# 1_3_prelab.net
KiCad netlist of a schematic drawn in Altium Designer
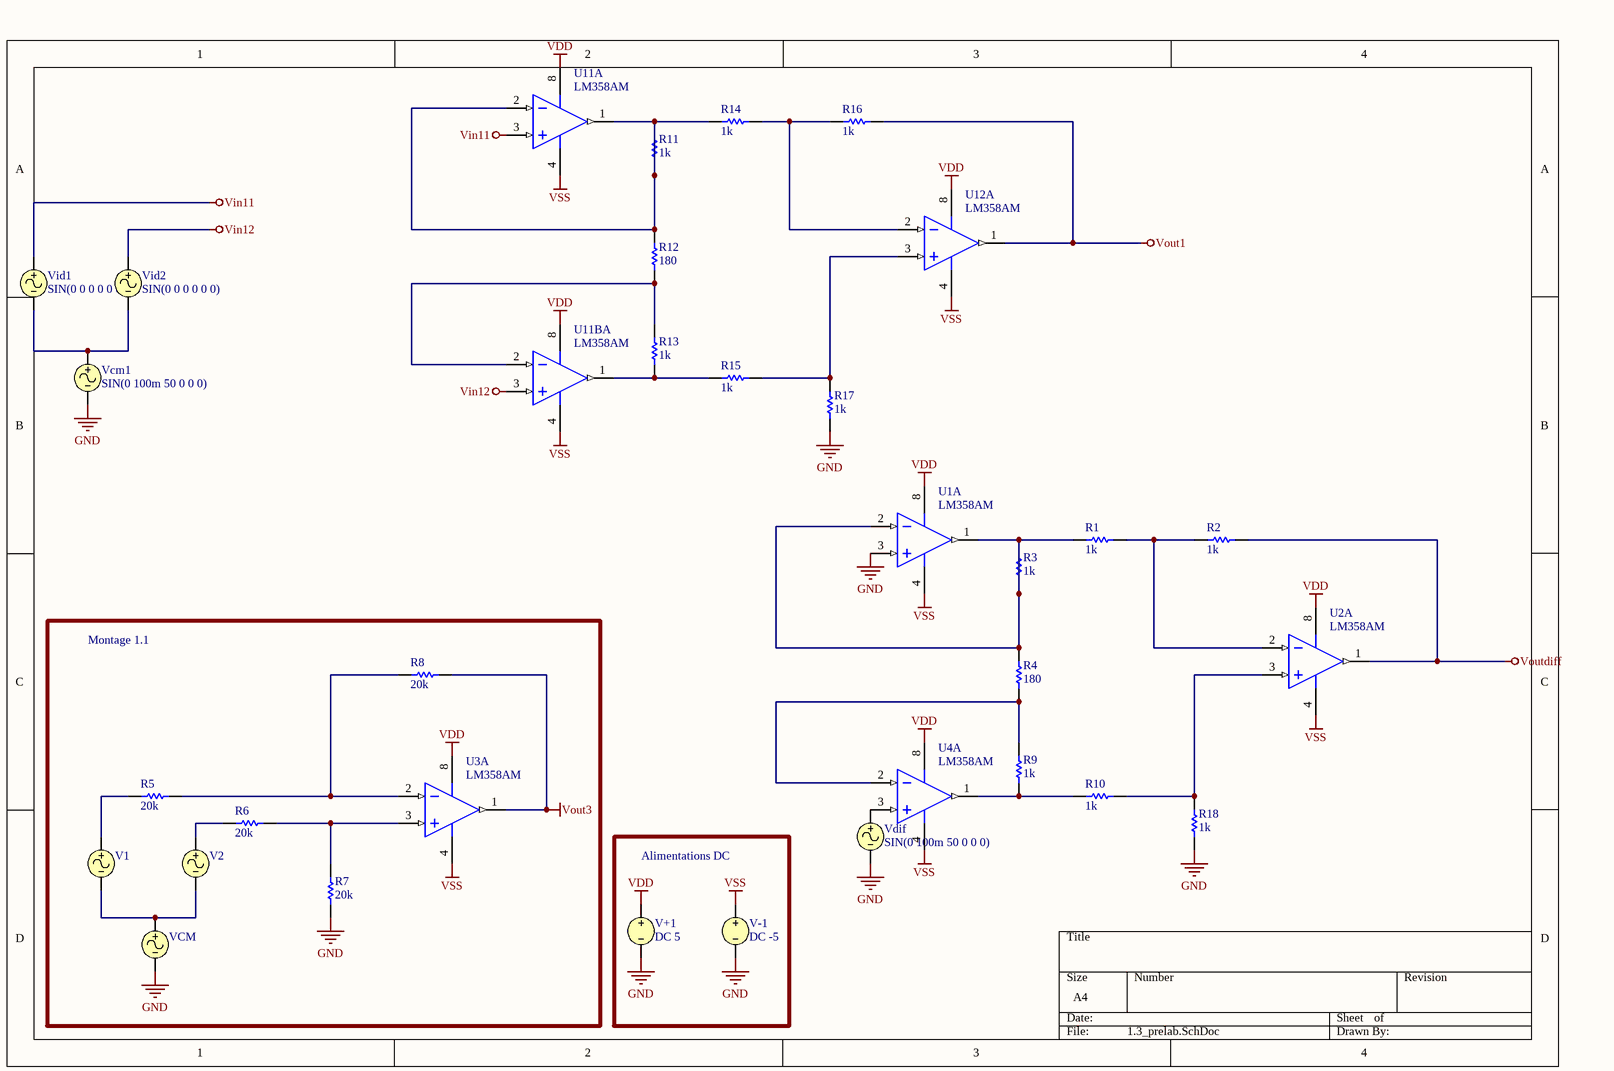
[diagram p0: 1.3_prelab.SchDoc]

(export (version "E")
  (design (tool "Eeschema 10.0.6"))
  (components
    (comp (ref "R1")
      (value "1k")
      (description "Resistor")
      (libsource (lib "Simulation Generic Components") (part "Resistor"))
    )
    (comp (ref "R2")
      (value "1k")
      (description "Resistor")
      (libsource (lib "Simulation Generic Components") (part "Resistor"))
    )
    (comp (ref "R3")
      (value "1k")
      (description "Resistor")
      (libsource (lib "Simulation Generic Components") (part "Resistor"))
    )
    (comp (ref "R4")
      (value "180")
      (description "Resistor")
      (libsource (lib "Simulation Generic Components") (part "Resistor"))
    )
    (comp (ref "R5")
      (value "20k")
      (description "Resistor")
      (libsource (lib "Simulation Generic Components") (part "Resistor"))
    )
    (comp (ref "R6")
      (value "20k")
      (description "Resistor")
      (libsource (lib "Simulation Generic Components") (part "Resistor"))
    )
    (comp (ref "R7")
      (value "20k")
      (description "Resistor")
      (libsource (lib "Simulation Generic Components") (part "Resistor"))
    )
    (comp (ref "R8")
      (value "20k")
      (description "Resistor")
      (libsource (lib "Simulation Generic Components") (part "Resistor"))
    )
    (comp (ref "R9")
      (value "1k")
      (description "Resistor")
      (libsource (lib "Simulation Generic Components") (part "Resistor"))
    )
    (comp (ref "R10")
      (value "1k")
      (description "Resistor")
      (libsource (lib "Simulation Generic Components") (part "Resistor"))
    )
    (comp (ref "R11")
      (value "1k")
      (description "Resistor")
      (libsource (lib "Simulation Generic Components") (part "Resistor"))
    )
    (comp (ref "R12")
      (value "180")
      (description "Resistor")
      (libsource (lib "Simulation Generic Components") (part "Resistor"))
    )
    (comp (ref "R13")
      (value "1k")
      (description "Resistor")
      (libsource (lib "Simulation Generic Components") (part "Resistor"))
    )
    (comp (ref "R14")
      (value "1k")
      (description "Resistor")
      (libsource (lib "Simulation Generic Components") (part "Resistor"))
    )
    (comp (ref "R15")
      (value "1k")
      (description "Resistor")
      (libsource (lib "Simulation Generic Components") (part "Resistor"))
    )
    (comp (ref "R16")
      (value "1k")
      (description "Resistor")
      (libsource (lib "Simulation Generic Components") (part "Resistor"))
    )
    (comp (ref "R17")
      (value "1k")
      (description "Resistor")
      (libsource (lib "Simulation Generic Components") (part "Resistor"))
    )
    (comp (ref "R18")
      (value "1k")
      (description "Resistor")
      (libsource (lib "Simulation Generic Components") (part "Resistor"))
    )
    (comp (ref "U1")
      (value "LM358AM")
      (footprint "M08A_N")
      (description "Low Power Dual Operational Amplifier")
      (fields
        (field (name "MANUFACTURER") "National Semiconductor")
        (field (name "DIGIKEYPARTNUMBER") "LM358AMXCT-ND")
        (field (name "PUBLISHER") "Altium Limited")
      )
      (libsource (lib "NSC Amplifier") (part "LM358AM"))
    )
    (comp (ref "U2")
      (value "LM358AM")
      (footprint "M08A_N")
      (description "Low Power Dual Operational Amplifier")
      (fields
        (field (name "MANUFACTURER") "National Semiconductor")
        (field (name "DIGIKEYPARTNUMBER") "LM358AMXCT-ND")
        (field (name "PUBLISHER") "Altium Limited")
      )
      (libsource (lib "NSC Amplifier") (part "LM358AM"))
    )
    (comp (ref "U3")
      (value "LM358AM")
      (footprint "M08A_N")
      (description "Low Power Dual Operational Amplifier")
      (fields
        (field (name "MANUFACTURER") "National Semiconductor")
        (field (name "DIGIKEYPARTNUMBER") "LM358AMXCT-ND")
        (field (name "PUBLISHER") "Altium Limited")
      )
      (libsource (lib "NSC Amplifier") (part "LM358AM"))
    )
    (comp (ref "U4")
      (value "LM358AM")
      (footprint "M08A_N")
      (description "Low Power Dual Operational Amplifier")
      (fields
        (field (name "MANUFACTURER") "National Semiconductor")
        (field (name "DIGIKEYPARTNUMBER") "LM358AMXCT-ND")
        (field (name "PUBLISHER") "Altium Limited")
      )
      (libsource (lib "NSC Amplifier") (part "LM358AM"))
    )
    (comp (ref "U11")
      (value "LM358AM")
      (footprint "M08A_N")
      (description "Low Power Dual Operational Amplifier")
      (fields
        (field (name "MANUFACTURER") "National Semiconductor")
        (field (name "DIGIKEYPARTNUMBER") "LM358AMXCT-ND")
        (field (name "PUBLISHER") "Altium Limited")
      )
      (libsource (lib "NSC Amplifier") (part "LM358AM"))
    )
    (comp (ref "U11B")
      (value "LM358AM")
      (footprint "M08A_N")
      (description "Low Power Dual Operational Amplifier")
      (fields
        (field (name "MANUFACTURER") "National Semiconductor")
        (field (name "DIGIKEYPARTNUMBER") "LM358AMXCT-ND")
        (field (name "PUBLISHER") "Altium Limited")
      )
      (libsource (lib "NSC Amplifier") (part "LM358AM"))
    )
    (comp (ref "U12")
      (value "LM358AM")
      (footprint "M08A_N")
      (description "Low Power Dual Operational Amplifier")
      (fields
        (field (name "MANUFACTURER") "National Semiconductor")
        (field (name "DIGIKEYPARTNUMBER") "LM358AMXCT-ND")
        (field (name "PUBLISHER") "Altium Limited")
      )
      (libsource (lib "NSC Amplifier") (part "LM358AM"))
    )
    (comp (ref "V+1")
      (value "DC 5")
      (description "Voltage Source")
      (fields (field (name "PUBLISHER") "Altium Limited"))
      (libsource (lib "Simulation Sources") (part "VSRC"))
    )
    (comp (ref "V-1")
      (value "DC -5")
      (description "Voltage Source")
      (fields (field (name "PUBLISHER") "Altium Limited"))
      (libsource (lib "Simulation Sources") (part "VSRC"))
    )
    (comp (ref "V1")
      (value "SIN(0 0 0 0 0 0)")
      (description "Sinusoidal Voltage Source")
      (fields (field (name "PUBLISHER") "Altium Limited"))
      (libsource (lib "Simulation Sources") (part "VSIN"))
    )
    (comp (ref "V2")
      (value "SIN(0 0 0 0 0 0)")
      (description "Sinusoidal Voltage Source")
      (fields (field (name "PUBLISHER") "Altium Limited"))
      (libsource (lib "Simulation Sources") (part "VSIN"))
    )
    (comp (ref "VCM")
      (value "SIN(0 0 0 0 0 0)")
      (description "Sinusoidal Voltage Source")
      (fields (field (name "PUBLISHER") "Altium Limited"))
      (libsource (lib "Simulation Sources") (part "VSIN"))
    )
    (comp (ref "Vcm1")
      (value "SIN(0 100m 50 0 0 0)")
      (description "Sinusoidal Voltage Source")
      (fields (field (name "PUBLISHER") "Altium Limited"))
      (libsource (lib "Simulation Sources") (part "VSIN"))
    )
    (comp (ref "Vdif")
      (value "SIN(0 100m 50 0 0 0)")
      (description "Sinusoidal Voltage Source")
      (fields (field (name "PUBLISHER") "Altium Limited"))
      (libsource (lib "Simulation Sources") (part "VSIN"))
    )
    (comp (ref "Vid1")
      (value "SIN(0 0 0 0 0 0)")
      (description "Sinusoidal Voltage Source")
      (fields (field (name "PUBLISHER") "Altium Limited"))
      (libsource (lib "Simulation Sources") (part "VSIN"))
    )
    (comp (ref "Vid2")
      (value "SIN(0 0 0 0 0 0)")
      (description "Sinusoidal Voltage Source")
      (fields (field (name "PUBLISHER") "Altium Limited"))
      (libsource (lib "Simulation Sources") (part "VSIN"))
    )
  )
  (nets
    (net (code "1") (name "GND") (class "Default")
      (node (ref "R17") (pin "1") (pinfunction "1_1") (pintype "passive"))
      (node (ref "R18") (pin "1") (pinfunction "1_1") (pintype "passive"))
      (node (ref "R7") (pin "1") (pinfunction "1_1") (pintype "passive"))
      (node (ref "U1") (pin "3") (pinfunction "INA+_3") (pintype "input"))
      (node (ref "V+1") (pin "2") (pinfunction "2_2") (pintype "passive"))
      (node (ref "V-1") (pin "2") (pinfunction "2_2") (pintype "passive"))
      (node (ref "VCM") (pin "2") (pinfunction "2_2") (pintype "passive"))
      (node (ref "Vcm1") (pin "2") (pinfunction "2_2") (pintype "passive"))
      (node (ref "Vdif") (pin "2") (pinfunction "2_2") (pintype "passive"))
    )
    (net (code "2") (name "Net-(R5-Pad1)") (class "Default")
      (node (ref "R5") (pin "1") (pinfunction "1_1") (pintype "passive"))
      (node (ref "V1") (pin "1") (pinfunction "1_1") (pintype "passive"))
    )
    (net (code "3") (name "Net-(R6-Pad1)") (class "Default")
      (node (ref "R6") (pin "1") (pinfunction "1_1") (pintype "passive"))
      (node (ref "V2") (pin "1") (pinfunction "1_1") (pintype "passive"))
    )
    (net (code "4") (name "Net-(U1A-INA-)") (class "Default")
      (node (ref "R1") (pin "2") (pinfunction "2_2") (pintype "passive"))
      (node (ref "R3") (pin "1") (pinfunction "1_1") (pintype "passive"))
      (node (ref "R3") (pin "2") (pinfunction "2_2") (pintype "passive"))
      (node (ref "R4") (pin "2") (pinfunction "2_2") (pintype "passive"))
      (node (ref "U1") (pin "1") (pinfunction "OUTA_1") (pintype "output"))
      (node (ref "U1") (pin "2") (pinfunction "INA-_2") (pintype "input"))
    )
    (net (code "5") (name "Net-(U2A-INA+)") (class "Default")
      (node (ref "R10") (pin "1") (pinfunction "1_1") (pintype "passive"))
      (node (ref "R18") (pin "2") (pinfunction "2_2") (pintype "passive"))
      (node (ref "U2") (pin "3") (pinfunction "INA+_3") (pintype "input"))
    )
    (net (code "6") (name "Net-(U2A-INA-)") (class "Default")
      (node (ref "R1") (pin "1") (pinfunction "1_1") (pintype "passive"))
      (node (ref "R2") (pin "2") (pinfunction "2_2") (pintype "passive"))
      (node (ref "U2") (pin "2") (pinfunction "INA-_2") (pintype "input"))
    )
    (net (code "7") (name "Net-(U3A-INA+)") (class "Default")
      (node (ref "R6") (pin "2") (pinfunction "2_2") (pintype "passive"))
      (node (ref "R7") (pin "2") (pinfunction "2_2") (pintype "passive"))
      (node (ref "U3") (pin "3") (pinfunction "INA+_3") (pintype "input"))
    )
    (net (code "8") (name "Net-(U3A-INA-)") (class "Default")
      (node (ref "R5") (pin "2") (pinfunction "2_2") (pintype "passive"))
      (node (ref "R8") (pin "1") (pinfunction "1_1") (pintype "passive"))
      (node (ref "U3") (pin "2") (pinfunction "INA-_2") (pintype "input"))
    )
    (net (code "9") (name "Net-(U4A-INA+)") (class "Default")
      (node (ref "U4") (pin "3") (pinfunction "INA+_3") (pintype "input"))
      (node (ref "Vdif") (pin "1") (pinfunction "1_1") (pintype "passive"))
    )
    (net (code "10") (name "Net-(U4A-INA-)") (class "Default")
      (node (ref "R4") (pin "1") (pinfunction "1_1") (pintype "passive"))
      (node (ref "R9") (pin "2") (pinfunction "2_2") (pintype "passive"))
      (node (ref "U4") (pin "2") (pinfunction "INA-_2") (pintype "input"))
    )
    (net (code "11") (name "Net-(U4A-OUTA)") (class "Default")
      (node (ref "R10") (pin "2") (pinfunction "2_2") (pintype "passive"))
      (node (ref "R9") (pin "1") (pinfunction "1_1") (pintype "passive"))
      (node (ref "U4") (pin "1") (pinfunction "OUTA_1") (pintype "output"))
    )
    (net (code "12") (name "Net-(U11A-INA-)") (class "Default")
      (node (ref "R11") (pin "1") (pinfunction "1_1") (pintype "passive"))
      (node (ref "R11") (pin "2") (pinfunction "2_2") (pintype "passive"))
      (node (ref "R12") (pin "2") (pinfunction "2_2") (pintype "passive"))
      (node (ref "R14") (pin "2") (pinfunction "2_2") (pintype "passive"))
      (node (ref "U11") (pin "1") (pinfunction "OUTA_1") (pintype "output"))
      (node (ref "U11") (pin "2") (pinfunction "INA-_2") (pintype "input"))
    )
    (net (code "13") (name "Net-(U11BA-INA-)") (class "Default")
      (node (ref "R12") (pin "1") (pinfunction "1_1") (pintype "passive"))
      (node (ref "R13") (pin "2") (pinfunction "2_2") (pintype "passive"))
      (node (ref "U11B") (pin "2") (pinfunction "INA-_2") (pintype "input"))
    )
    (net (code "14") (name "Net-(U11BA-OUTA)") (class "Default")
      (node (ref "R13") (pin "1") (pinfunction "1_1") (pintype "passive"))
      (node (ref "R15") (pin "2") (pinfunction "2_2") (pintype "passive"))
      (node (ref "U11B") (pin "1") (pinfunction "OUTA_1") (pintype "output"))
    )
    (net (code "15") (name "Net-(U12A-INA+)") (class "Default")
      (node (ref "R15") (pin "1") (pinfunction "1_1") (pintype "passive"))
      (node (ref "R17") (pin "2") (pinfunction "2_2") (pintype "passive"))
      (node (ref "U12") (pin "3") (pinfunction "INA+_3") (pintype "input"))
    )
    (net (code "16") (name "Net-(U12A-INA-)") (class "Default")
      (node (ref "R14") (pin "1") (pinfunction "1_1") (pintype "passive"))
      (node (ref "R16") (pin "2") (pinfunction "2_2") (pintype "passive"))
      (node (ref "U12") (pin "2") (pinfunction "INA-_2") (pintype "input"))
    )
    (net (code "17") (name "Net-(V1-Pad2)") (class "Default")
      (node (ref "V1") (pin "2") (pinfunction "2_2") (pintype "passive"))
      (node (ref "V2") (pin "2") (pinfunction "2_2") (pintype "passive"))
      (node (ref "VCM") (pin "1") (pinfunction "1_1") (pintype "passive"))
    )
    (net (code "18") (name "Net-(Vcm1-Pad1)") (class "Default")
      (node (ref "Vcm1") (pin "1") (pinfunction "1_1") (pintype "passive"))
      (node (ref "Vid1") (pin "2") (pinfunction "2_2") (pintype "passive"))
      (node (ref "Vid2") (pin "2") (pinfunction "2_2") (pintype "passive"))
    )
    (net (code "19") (name "VDD") (class "Default")
      (node (ref "U1") (pin "8") (pinfunction "V+_8") (pintype "power_in"))
      (node (ref "U11") (pin "8") (pinfunction "V+_8") (pintype "power_in"))
      (node (ref "U11B") (pin "8") (pinfunction "V+_8") (pintype "power_in"))
      (node (ref "U12") (pin "8") (pinfunction "V+_8") (pintype "power_in"))
      (node (ref "U2") (pin "8") (pinfunction "V+_8") (pintype "power_in"))
      (node (ref "U3") (pin "8") (pinfunction "V+_8") (pintype "power_in"))
      (node (ref "U4") (pin "8") (pinfunction "V+_8") (pintype "power_in"))
      (node (ref "V+1") (pin "1") (pinfunction "1_1") (pintype "passive"))
    )
    (net (code "20") (name "VSS") (class "Default")
      (node (ref "U1") (pin "4") (pinfunction "GND_4") (pintype "power_in"))
      (node (ref "U11") (pin "4") (pinfunction "GND_4") (pintype "power_in"))
      (node (ref "U11B") (pin "4") (pinfunction "GND_4") (pintype "power_in"))
      (node (ref "U12") (pin "4") (pinfunction "GND_4") (pintype "power_in"))
      (node (ref "U2") (pin "4") (pinfunction "GND_4") (pintype "power_in"))
      (node (ref "U3") (pin "4") (pinfunction "GND_4") (pintype "power_in"))
      (node (ref "U4") (pin "4") (pinfunction "GND_4") (pintype "power_in"))
      (node (ref "V-1") (pin "1") (pinfunction "1_1") (pintype "passive"))
    )
    (net (code "21") (name "Vin11") (class "Default")
      (node (ref "U11") (pin "3") (pinfunction "INA+_3") (pintype "input"))
      (node (ref "Vid1") (pin "1") (pinfunction "1_1") (pintype "passive"))
    )
    (net (code "22") (name "Vin12") (class "Default")
      (node (ref "U11B") (pin "3") (pinfunction "INA+_3") (pintype "input"))
      (node (ref "Vid2") (pin "1") (pinfunction "1_1") (pintype "passive"))
    )
    (net (code "23") (name "Vout1") (class "Default")
      (node (ref "R16") (pin "1") (pinfunction "1_1") (pintype "passive"))
      (node (ref "U12") (pin "1") (pinfunction "OUTA_1") (pintype "output"))
    )
    (net (code "24") (name "Vout3") (class "Default")
      (node (ref "R8") (pin "2") (pinfunction "2_2") (pintype "passive"))
      (node (ref "U3") (pin "1") (pinfunction "OUTA_1") (pintype "output"))
    )
    (net (code "25") (name "Voutdiff") (class "Default")
      (node (ref "R2") (pin "1") (pinfunction "1_1") (pintype "passive"))
      (node (ref "U2") (pin "1") (pinfunction "OUTA_1") (pintype "output"))
    )
  )
)
